# smps.net
KiCad netlist of a schematic drawn in EAGLE
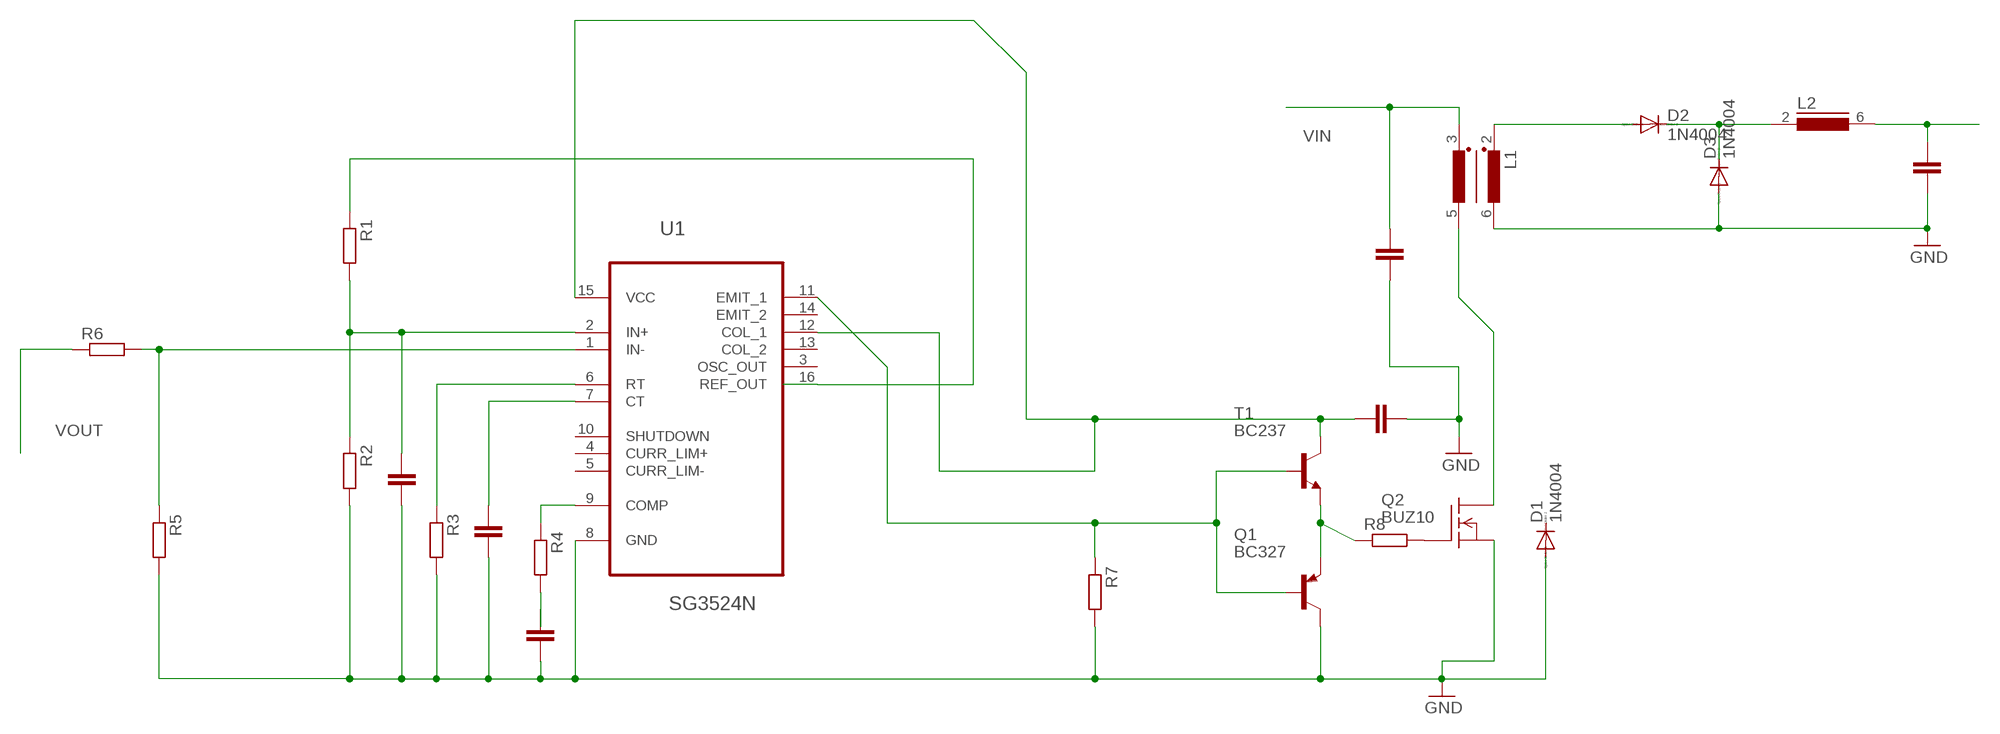
[diagram p0: schematic, sheet 1]

(export (version "E")
  (design (tool "Eeschema 10.0.6"))
  (components
    (comp (ref "D1")
      (value "1N4004")
      (footprint "eagle-import:DO41-10")
      (libsource (lib "eagle-import") (part "1N4004"))
    )
    (comp (ref "D2")
      (value "1N4004")
      (footprint "eagle-import:DO41-10")
      (libsource (lib "eagle-import") (part "1N4004"))
    )
    (comp (ref "D3")
      (value "1N4004")
      (footprint "eagle-import:DO41-10")
      (libsource (lib "eagle-import") (part "1N4004"))
    )
    (comp (ref "L1")
      (value "RM6-2")
      (footprint "eagle-import:RM5-4")
      (libsource (lib "eagle-import") (part "RM6-2"))
    )
    (comp (ref "L2")
      (value "RM6")
      (footprint "eagle-import:RM6-4")
      (libsource (lib "eagle-import") (part "RM6"))
    )
    (comp (ref "Q1")
      (value "BC327")
      (footprint "eagle-import:TO92")
      (libsource (lib "eagle-import") (part "BC327"))
    )
    (comp (ref "Q2")
      (value "BUZ10")
      (footprint "eagle-import:TO220")
      (libsource (lib "eagle-import") (part "BUZ10"))
    )
    (comp (ref "R1")
      (value "R-EU_0204/7")
      (footprint "eagle-import:0204_7")
      (libsource (lib "eagle-import") (part "R-EU_0204/7"))
    )
    (comp (ref "R2")
      (value "R-EU_0204/7")
      (footprint "eagle-import:0204_7")
      (libsource (lib "eagle-import") (part "R-EU_0204/7"))
    )
    (comp (ref "R3")
      (value "R-EU_0204/7")
      (footprint "eagle-import:0204_7")
      (libsource (lib "eagle-import") (part "R-EU_0204/7"))
    )
    (comp (ref "R4")
      (value "R-EU_0204/7")
      (footprint "eagle-import:0204_7")
      (libsource (lib "eagle-import") (part "R-EU_0204/7"))
    )
    (comp (ref "R5")
      (value "R-EU_0204/7")
      (footprint "eagle-import:0204_7")
      (libsource (lib "eagle-import") (part "R-EU_0204/7"))
    )
    (comp (ref "R6")
      (value "R-EU_0204/7")
      (footprint "eagle-import:0204_7")
      (libsource (lib "eagle-import") (part "R-EU_0204/7"))
    )
    (comp (ref "R7")
      (value "R-EU_0204/7")
      (footprint "eagle-import:0204_7")
      (libsource (lib "eagle-import") (part "R-EU_0204/7"))
    )
    (comp (ref "R8")
      (value "R-EU_0204/7")
      (footprint "eagle-import:0204_7")
      (libsource (lib "eagle-import") (part "R-EU_0204/7"))
    )
    (comp (ref "T1")
      (value "BC237")
      (footprint "eagle-import:TO92")
      (libsource (lib "eagle-import") (part "BC237"))
    )
    (comp (ref "U1")
      (value "SG3524N")
      (footprint "eagle-import:DIP254P762X508-16")
      (libsource (lib "eagle-import") (part "SG3524N"))
    )
  )
  (nets
    (net (code "1") (name "/VIN") (class "Default")
      (node (ref "L1") (pin "3") (pinfunction "W2A_3") (pintype "passive"))
    )
    (net (code "2") (name "/VOUT") (class "Default")
      (node (ref "L2") (pin "6") (pinfunction "2_6") (pintype "passive"))
      (node (ref "R6") (pin "1") (pinfunction "1_1") (pintype "passive"))
    )
    (net (code "3") (name "GND") (class "Default")
      (node (ref "D1") (pin "A") (pinfunction "A_A") (pintype "passive"))
      (node (ref "D3") (pin "A") (pinfunction "A_A") (pintype "passive"))
      (node (ref "L1") (pin "6") (pinfunction "W1E_6") (pintype "passive"))
      (node (ref "Q1") (pin "3") (pinfunction "C_3") (pintype "passive"))
      (node (ref "Q2") (pin "3") (pinfunction "S_3") (pintype "passive"))
      (node (ref "R2") (pin "2") (pinfunction "2_2") (pintype "passive"))
      (node (ref "R3") (pin "2") (pinfunction "2_2") (pintype "passive"))
      (node (ref "R5") (pin "2") (pinfunction "2_2") (pintype "passive"))
      (node (ref "R7") (pin "2") (pinfunction "2_2") (pintype "passive"))
      (node (ref "U1") (pin "8") (pinfunction "GND_8") (pintype "passive"))
    )
    (net (code "4") (name "Net-(L1-W1A)") (class "Default")
      (node (ref "D2") (pin "A") (pinfunction "A_A") (pintype "passive"))
      (node (ref "L1") (pin "2") (pinfunction "W1A_2") (pintype "passive"))
    )
    (net (code "5") (name "Net-(L1-W2E)") (class "Default")
      (node (ref "L1") (pin "5") (pinfunction "W2E_5") (pintype "passive"))
      (node (ref "Q2") (pin "2") (pinfunction "D_2") (pintype "passive"))
    )
    (net (code "6") (name "Net-(L2-1)") (class "Default")
      (node (ref "D2") (pin "C") (pinfunction "C_C") (pintype "passive"))
      (node (ref "D3") (pin "C") (pinfunction "C_C") (pintype "passive"))
      (node (ref "L2") (pin "2") (pinfunction "1_2") (pintype "passive"))
    )
    (net (code "7") (name "Net-(Q1-B)") (class "Default")
      (node (ref "Q1") (pin "2") (pinfunction "B_2") (pintype "passive"))
      (node (ref "R7") (pin "1") (pinfunction "1_1") (pintype "passive"))
      (node (ref "T1") (pin "2") (pinfunction "B_2") (pintype "passive"))
      (node (ref "U1") (pin "11") (pinfunction "EMIT_1_11") (pintype "passive"))
    )
    (net (code "8") (name "Net-(Q1-E)") (class "Default")
      (node (ref "Q1") (pin "1") (pinfunction "E_1") (pintype "passive"))
      (node (ref "R8") (pin "1") (pinfunction "1_1") (pintype "passive"))
      (node (ref "T1") (pin "1") (pinfunction "E_1") (pintype "passive"))
    )
    (net (code "9") (name "Net-(Q2-G)") (class "Default")
      (node (ref "Q2") (pin "1") (pinfunction "G_1") (pintype "passive"))
      (node (ref "R8") (pin "2") (pinfunction "2_2") (pintype "passive"))
    )
    (net (code "10") (name "Net-(T1-C)") (class "Default")
      (node (ref "T1") (pin "3") (pinfunction "C_3") (pintype "passive"))
      (node (ref "U1") (pin "12") (pinfunction "COL_1_12") (pintype "passive"))
      (node (ref "U1") (pin "15") (pinfunction "VCC_15") (pintype "power_in"))
    )
    (net (code "11") (name "Net-(U1-COMP)") (class "Default")
      (node (ref "R4") (pin "1") (pinfunction "1_1") (pintype "passive"))
      (node (ref "U1") (pin "9") (pinfunction "COMP_9") (pintype "passive"))
    )
    (net (code "12") (name "Net-(U1-IN+)") (class "Default")
      (node (ref "R1") (pin "2") (pinfunction "2_2") (pintype "passive"))
      (node (ref "R2") (pin "1") (pinfunction "1_1") (pintype "passive"))
      (node (ref "U1") (pin "2") (pinfunction "IN+_2") (pintype "input"))
    )
    (net (code "13") (name "Net-(U1-IN-)") (class "Default")
      (node (ref "R5") (pin "1") (pinfunction "1_1") (pintype "passive"))
      (node (ref "R6") (pin "2") (pinfunction "2_2") (pintype "passive"))
      (node (ref "U1") (pin "1") (pinfunction "IN-_1") (pintype "input"))
    )
    (net (code "14") (name "Net-(U1-REF_OUT)") (class "Default")
      (node (ref "R1") (pin "1") (pinfunction "1_1") (pintype "passive"))
      (node (ref "U1") (pin "16") (pinfunction "REF_OUT_16") (pintype "output"))
    )
    (net (code "15") (name "Net-(U1-RT)") (class "Default")
      (node (ref "R3") (pin "1") (pinfunction "1_1") (pintype "passive"))
      (node (ref "U1") (pin "6") (pinfunction "RT_6") (pintype "input"))
    )
    (net (code "16") (name "unconnected-(D1-PadC)") (class "Default")
      (node (ref "D1") (pin "C") (pinfunction "C_C") (pintype "passive"))
    )
    (net (code "17") (name "unconnected-(R4-Pad2)") (class "Default")
      (node (ref "R4") (pin "2") (pinfunction "2_2") (pintype "passive"))
    )
    (net (code "18") (name "unconnected-(U1-COL_2-Pad13)") (class "Default")
      (node (ref "U1") (pin "13") (pinfunction "COL_2_13") (pintype "passive"))
    )
    (net (code "19") (name "unconnected-(U1-CT-Pad7)") (class "Default")
      (node (ref "U1") (pin "7") (pinfunction "CT_7") (pintype "input"))
    )
    (net (code "20") (name "unconnected-(U1-CURR_LIM+-Pad4)") (class "Default")
      (node (ref "U1") (pin "4") (pinfunction "CURR_LIM+_4") (pintype "input"))
    )
    (net (code "21") (name "unconnected-(U1-CURR_LIM--Pad5)") (class "Default")
      (node (ref "U1") (pin "5") (pinfunction "CURR_LIM-_5") (pintype "input"))
    )
    (net (code "22") (name "unconnected-(U1-EMIT_2-Pad14)") (class "Default")
      (node (ref "U1") (pin "14") (pinfunction "EMIT_2_14") (pintype "passive"))
    )
    (net (code "23") (name "unconnected-(U1-OSC_OUT-Pad3)") (class "Default")
      (node (ref "U1") (pin "3") (pinfunction "OSC_OUT_3") (pintype "output"))
    )
    (net (code "24") (name "unconnected-(U1-SHUTDOWN-Pad10)") (class "Default")
      (node (ref "U1") (pin "10") (pinfunction "SHUTDOWN_10") (pintype "input"))
    )
  )
)
